# Collar.net
KiCad netlist of a schematic drawn in Altium Designer
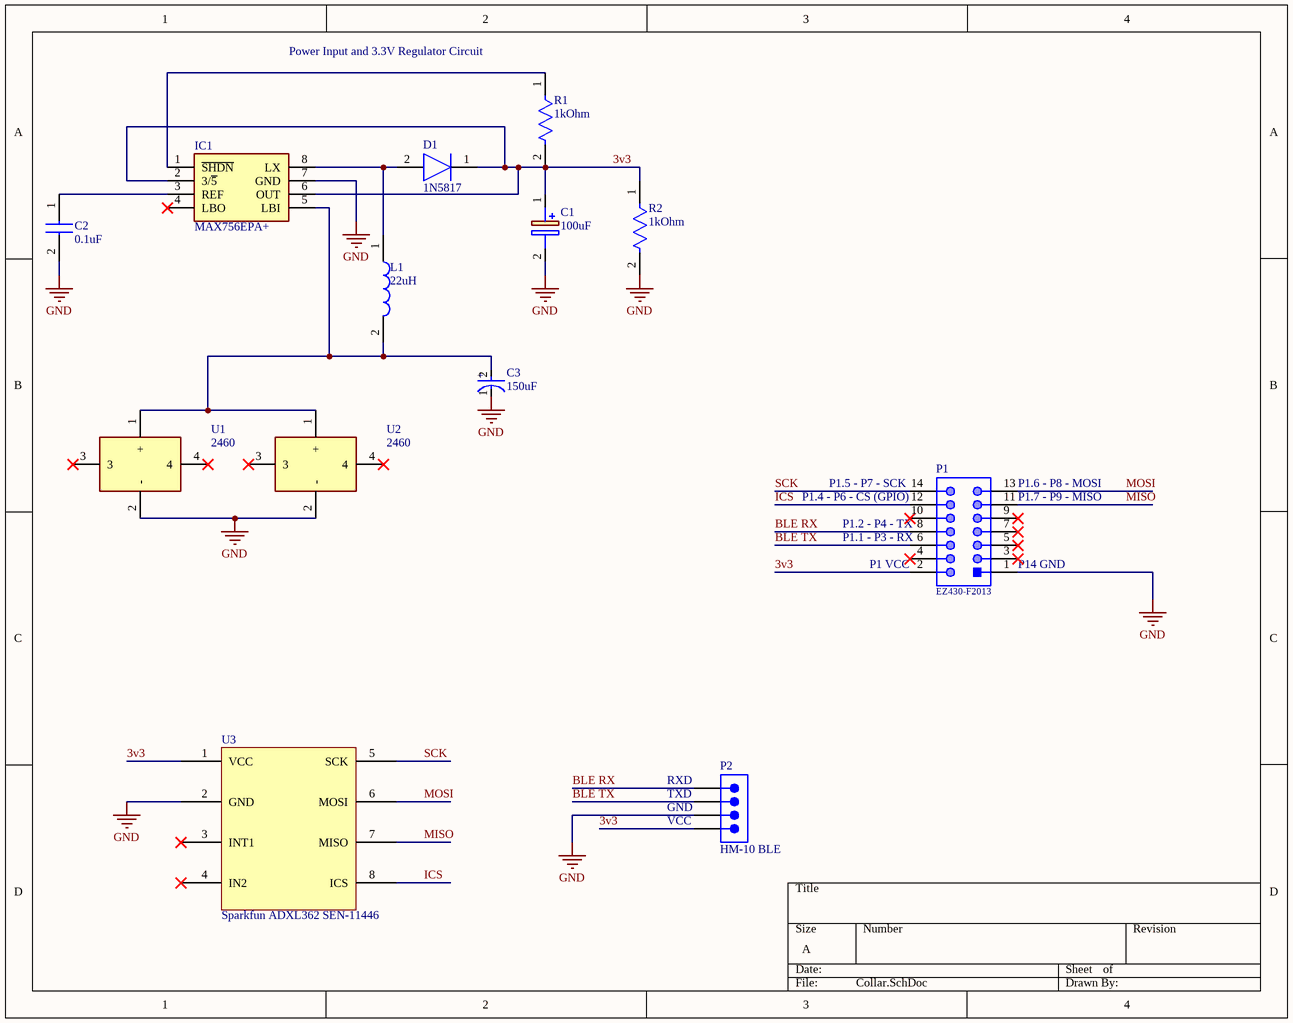
[diagram p0: Collar.SchDoc]

(export (version "E")
  (design (tool "Eeschema 10.0.6"))
  (components
    (comp (ref "C1")
      (value "100uF")
      (footprint "SamacSys:CAPPRD200W50D550H1250")
      (description "Capacitor Polarised")
      (fields (field (name "MANUFACTURER_PART_NUMBER") "107CKE025MEM"))
      (libsource (lib "*") (part "107CKE025MEM"))
    )
    (comp (ref "C2")
      (value "0.1uF")
      (footprint "SamacSys:K104K10X7RF5UH5")
      (description "Capacitor")
      (fields
        (field (name "MANUFACTURER_PART_NUMBER") "K104K10X7RF5UH5")
        (field (name "MOUSER PART NUMBER") "594-K104K10X7RF5UH5")
      )
      (libsource (lib "SamacSys") (part "K104K10X7RF5UH5"))
    )
    (comp (ref "C3")
      (value "150uF")
      (footprint "FP-UCY2V151MHD-MFG")
      (description "CAP ALUM 150UF 20% 350V RADIAL")
      (fields (field (name "TOLERANCE") "20%"))
      (libsource (lib "Altium Content Vault") (part "203bc49f2ac43e59fd269a8c329ed05"))
    )
    (comp (ref "D1")
      (value "1N5817")
      (footprint "SamacSys:DIOAD1405W86L465D235")
      (description "Diode")
      (fields (field (name "MOUSER PART NUMBER") "512-1N5817"))
      (libsource (lib "*") (part "1N5817"))
    )
    (comp (ref "IC1")
      (value "MAX756EPA+")
      (footprint "SamacSys:DIP794W56P254L938H457Q8N")
      (description "Integrated Circuit")
      (fields (field (name "MOUSER PART NUMBER") "700-MAX756EPA"))
      (libsource (lib "*") (part "MAX756EPA+"))
    )
    (comp (ref "L1")
      (value "22uH")
      (footprint "SamacSys:INDAD2550W80L950D400")
      (description "Inductor")
      (fields
        (field (name "MANUFACTURER_PART_NUMBER") "B78108E1223K000")
        (field (name "MOUSER PART NUMBER") "871-B78108E1223K000")
      )
      (libsource (lib "*") (part "B78108E1223K000"))
    )
    (comp (ref "P1")
      (value "EZ430-F2013")
      (footprint "61301421121")
      (description "THT Vertical Pin Header WR-PHD, Pitch 2.54 mm, Dual Row, 14 pins")
      (fields
        (field (name "PART NUMBER") "61301421121")
        (field (name "MANUFACTURER") "Wurth Elektronik")
        (field (name "PUBLISHER") "WurthElektronik")
      )
      (libsource (lib "Altium Content Vault") (part "WE-CN-2P-M-R14"))
    )
    (comp (ref "P2")
      (value "HM-10 BLE")
      (footprint "SMTC-TSW-104-08-X-S")
      (description "0.025\" SQ Post Header, Through-hole, Vertical, -55 to 125 degC, 2.54 mm Pitch, 4-Pin, Male, RoHS")
      (fields (field (name "MANUFACTURER") "Samtec") (field (name "PARTNUMBER") "TSW-104-08-G-S"))
      (libsource (lib "Altium Content Vault") (part "SMTC-TSW-104-08-X-S"))
    )
    (comp (ref "R1")
      (value "1kOhm")
      (footprint "FP-MRS25-MFG")
      (description "RES 1.1K OHM 0.6W 1% AXIAL")
      (fields
        (field (name "MANUFACTURER") "Vishay BC Components")
        (field (name "OCTOPART") "https://octopart.com/mrs25000c1101fct00-vishay-43740214")
      )
      (libsource (lib "Altium Content Vault") (part "1029c3af85768c4190bb7ad29bc67b5"))
    )
    (comp (ref "R2")
      (value "1kOhm")
      (footprint "FP-MRS25-MFG")
      (description "RES 1.1K OHM 0.6W 1% AXIAL")
      (fields
        (field (name "MANUFACTURER") "Vishay BC Components")
        (field (name "OCTOPART") "https://octopart.com/mrs25000c1101fct00-vishay-43740214")
      )
      (libsource (lib "Altium Content Vault") (part "1029c3af85768c4190bb7ad29bc67b5"))
    )
    (comp (ref "U1")
      (value "2460")
      (footprint "SamacSys:2460")
      (description "Undefined or Miscellaneous")
      (fields (field (name "MOUSER PART NUMBER") "534-2460"))
      (libsource (lib "*") (part "2460"))
    )
    (comp (ref "U2")
      (value "2460")
      (footprint "SamacSys:2460")
      (description "Undefined or Miscellaneous")
      (fields (field (name "MOUSER PART NUMBER") "534-2460"))
      (libsource (lib "*") (part "2460"))
    )
    (comp (ref "U3")
      (value "Sparkfun ADXL362 SEN-11446")
      (footprint "ADXL362 Breakout Board")
      (description "ADXL362 Breakout Board")
      (libsource (lib "Waterboy_Library") (part "ADXL362 Breakout Board"))
    )
  )
  (nets
    (net (code "1") (name "/3v3") (class "Default")
      (node (ref "C1") (pin "1") (pinfunction "+_1") (pintype "passive"))
      (node (ref "D1") (pin "1") (pinfunction "K_1") (pintype "passive"))
      (node (ref "IC1") (pin "2") (pinfunction "3/~{5}_2") (pintype "passive"))
      (node (ref "IC1") (pin "6") (pinfunction "OUT_6") (pintype "passive"))
      (node (ref "P1") (pin "2") (pinfunction "P1_2") (pintype "passive"))
      (node (ref "P2") (pin "1") (pinfunction "VCC_1") (pintype "passive"))
      (node (ref "R1") (pin "2") (pinfunction "2_2") (pintype "passive"))
      (node (ref "R2") (pin "1") (pinfunction "1_1") (pintype "passive"))
      (node (ref "U3") (pin "1") (pinfunction "VCC_1") (pintype "passive"))
    )
    (net (code "2") (name "/BLE RX") (class "Default")
      (node (ref "P1") (pin "8") (pinfunction "P4_8") (pintype "passive"))
      (node (ref "P2") (pin "4") (pinfunction "RXD_4") (pintype "passive"))
    )
    (net (code "3") (name "/BLE TX") (class "Default")
      (node (ref "P1") (pin "6") (pinfunction "P3_6") (pintype "passive"))
      (node (ref "P2") (pin "3") (pinfunction "TXD_3") (pintype "passive"))
    )
    (net (code "4") (name "/ICS") (class "Default")
      (node (ref "P1") (pin "12") (pinfunction "P6_12") (pintype "passive"))
      (node (ref "U3") (pin "8") (pinfunction "ICS_8") (pintype "passive"))
    )
    (net (code "5") (name "/MISO") (class "Default")
      (node (ref "P1") (pin "11") (pinfunction "P9_11") (pintype "passive"))
      (node (ref "U3") (pin "7") (pinfunction "MISO_7") (pintype "passive"))
    )
    (net (code "6") (name "/MOSI") (class "Default")
      (node (ref "P1") (pin "13") (pinfunction "P8_13") (pintype "passive"))
      (node (ref "U3") (pin "6") (pinfunction "MOSI_6") (pintype "passive"))
    )
    (net (code "7") (name "/SCK") (class "Default")
      (node (ref "P1") (pin "14") (pinfunction "P7_14") (pintype "passive"))
      (node (ref "U3") (pin "5") (pinfunction "SCK_5") (pintype "passive"))
    )
    (net (code "8") (name "GND") (class "Default")
      (node (ref "C1") (pin "2") (pinfunction "-_2") (pintype "passive"))
      (node (ref "C2") (pin "2") (pinfunction "2_2") (pintype "passive"))
      (node (ref "C3") (pin "1") (pinfunction "C_1") (pintype "passive"))
      (node (ref "IC1") (pin "7") (pinfunction "GND_7") (pintype "passive"))
      (node (ref "P1") (pin "1") (pinfunction "P14_1") (pintype "passive"))
      (node (ref "P2") (pin "2") (pinfunction "GND_2") (pintype "passive"))
      (node (ref "R2") (pin "2") (pinfunction "2_2") (pintype "passive"))
      (node (ref "U1") (pin "2") (pinfunction "-_2") (pintype "passive"))
      (node (ref "U2") (pin "2") (pinfunction "-_2") (pintype "passive"))
      (node (ref "U3") (pin "2") (pinfunction "GND_2") (pintype "passive"))
    )
    (net (code "9") (name "Net-(C3-A)") (class "Default")
      (node (ref "C3") (pin "2") (pinfunction "A_2") (pintype "passive"))
      (node (ref "IC1") (pin "5") (pinfunction "LBI_5") (pintype "passive"))
      (node (ref "L1") (pin "2") (pinfunction "2_2") (pintype "passive"))
      (node (ref "U1") (pin "1") (pinfunction "+_1") (pintype "passive"))
      (node (ref "U2") (pin "1") (pinfunction "+_1") (pintype "passive"))
    )
    (net (code "10") (name "Net-(D1-A)") (class "Default")
      (node (ref "D1") (pin "2") (pinfunction "A_2") (pintype "passive"))
      (node (ref "IC1") (pin "8") (pinfunction "LX_8") (pintype "passive"))
      (node (ref "L1") (pin "1") (pinfunction "1_1") (pintype "passive"))
    )
    (net (code "11") (name "Net-(IC1-REF)") (class "Default")
      (node (ref "C2") (pin "1") (pinfunction "1_1") (pintype "passive"))
      (node (ref "IC1") (pin "3") (pinfunction "REF_3") (pintype "passive"))
    )
    (net (code "12") (name "Net-(IC1-~{SHDN})") (class "Default")
      (node (ref "IC1") (pin "1") (pinfunction "~{SHDN}_1") (pintype "passive"))
      (node (ref "R1") (pin "1") (pinfunction "1_1") (pintype "passive"))
    )
    (net (code "13") (name "unconnected-(IC1-LBO-Pad4)") (class "Default")
      (node (ref "IC1") (pin "4") (pinfunction "LBO_4") (pintype "passive+no_connect"))
    )
    (net (code "14") (name "unconnected-(P1-P2-Pad4)") (class "Default")
      (node (ref "P1") (pin "4") (pinfunction "P2_4") (pintype "passive+no_connect"))
    )
    (net (code "15") (name "unconnected-(P1-P5-Pad10)") (class "Default")
      (node (ref "P1") (pin "10") (pinfunction "P5_10") (pintype "passive+no_connect"))
    )
    (net (code "16") (name "unconnected-(P1-P10-Pad9)") (class "Default")
      (node (ref "P1") (pin "9") (pinfunction "P10_9") (pintype "passive+no_connect"))
    )
    (net (code "17") (name "unconnected-(P1-P11-Pad7)") (class "Default")
      (node (ref "P1") (pin "7") (pinfunction "P11_7") (pintype "passive+no_connect"))
    )
    (net (code "18") (name "unconnected-(P1-P12-Pad5)") (class "Default")
      (node (ref "P1") (pin "5") (pinfunction "P12_5") (pintype "passive+no_connect"))
    )
    (net (code "19") (name "unconnected-(P1-P13-Pad3)") (class "Default")
      (node (ref "P1") (pin "3") (pinfunction "P13_3") (pintype "passive+no_connect"))
    )
    (net (code "20") (name "unconnected-(U1-Pad3)") (class "Default")
      (node (ref "U1") (pin "3") (pinfunction "3_3") (pintype "passive+no_connect"))
    )
    (net (code "21") (name "unconnected-(U1-Pad4)") (class "Default")
      (node (ref "U1") (pin "4") (pinfunction "4_4") (pintype "passive+no_connect"))
    )
    (net (code "22") (name "unconnected-(U2-Pad3)") (class "Default")
      (node (ref "U2") (pin "3") (pinfunction "3_3") (pintype "passive+no_connect"))
    )
    (net (code "23") (name "unconnected-(U2-Pad4)") (class "Default")
      (node (ref "U2") (pin "4") (pinfunction "4_4") (pintype "passive+no_connect"))
    )
    (net (code "24") (name "unconnected-(U3-IN2-Pad4)") (class "Default")
      (node (ref "U3") (pin "4") (pinfunction "IN2_4") (pintype "passive+no_connect"))
    )
    (net (code "25") (name "unconnected-(U3-INT1-Pad3)") (class "Default")
      (node (ref "U3") (pin "3") (pinfunction "INT1_3") (pintype "passive+no_connect"))
    )
  )
)
